# CONNECTOR.net
KiCad netlist of a schematic drawn in Altium Designer
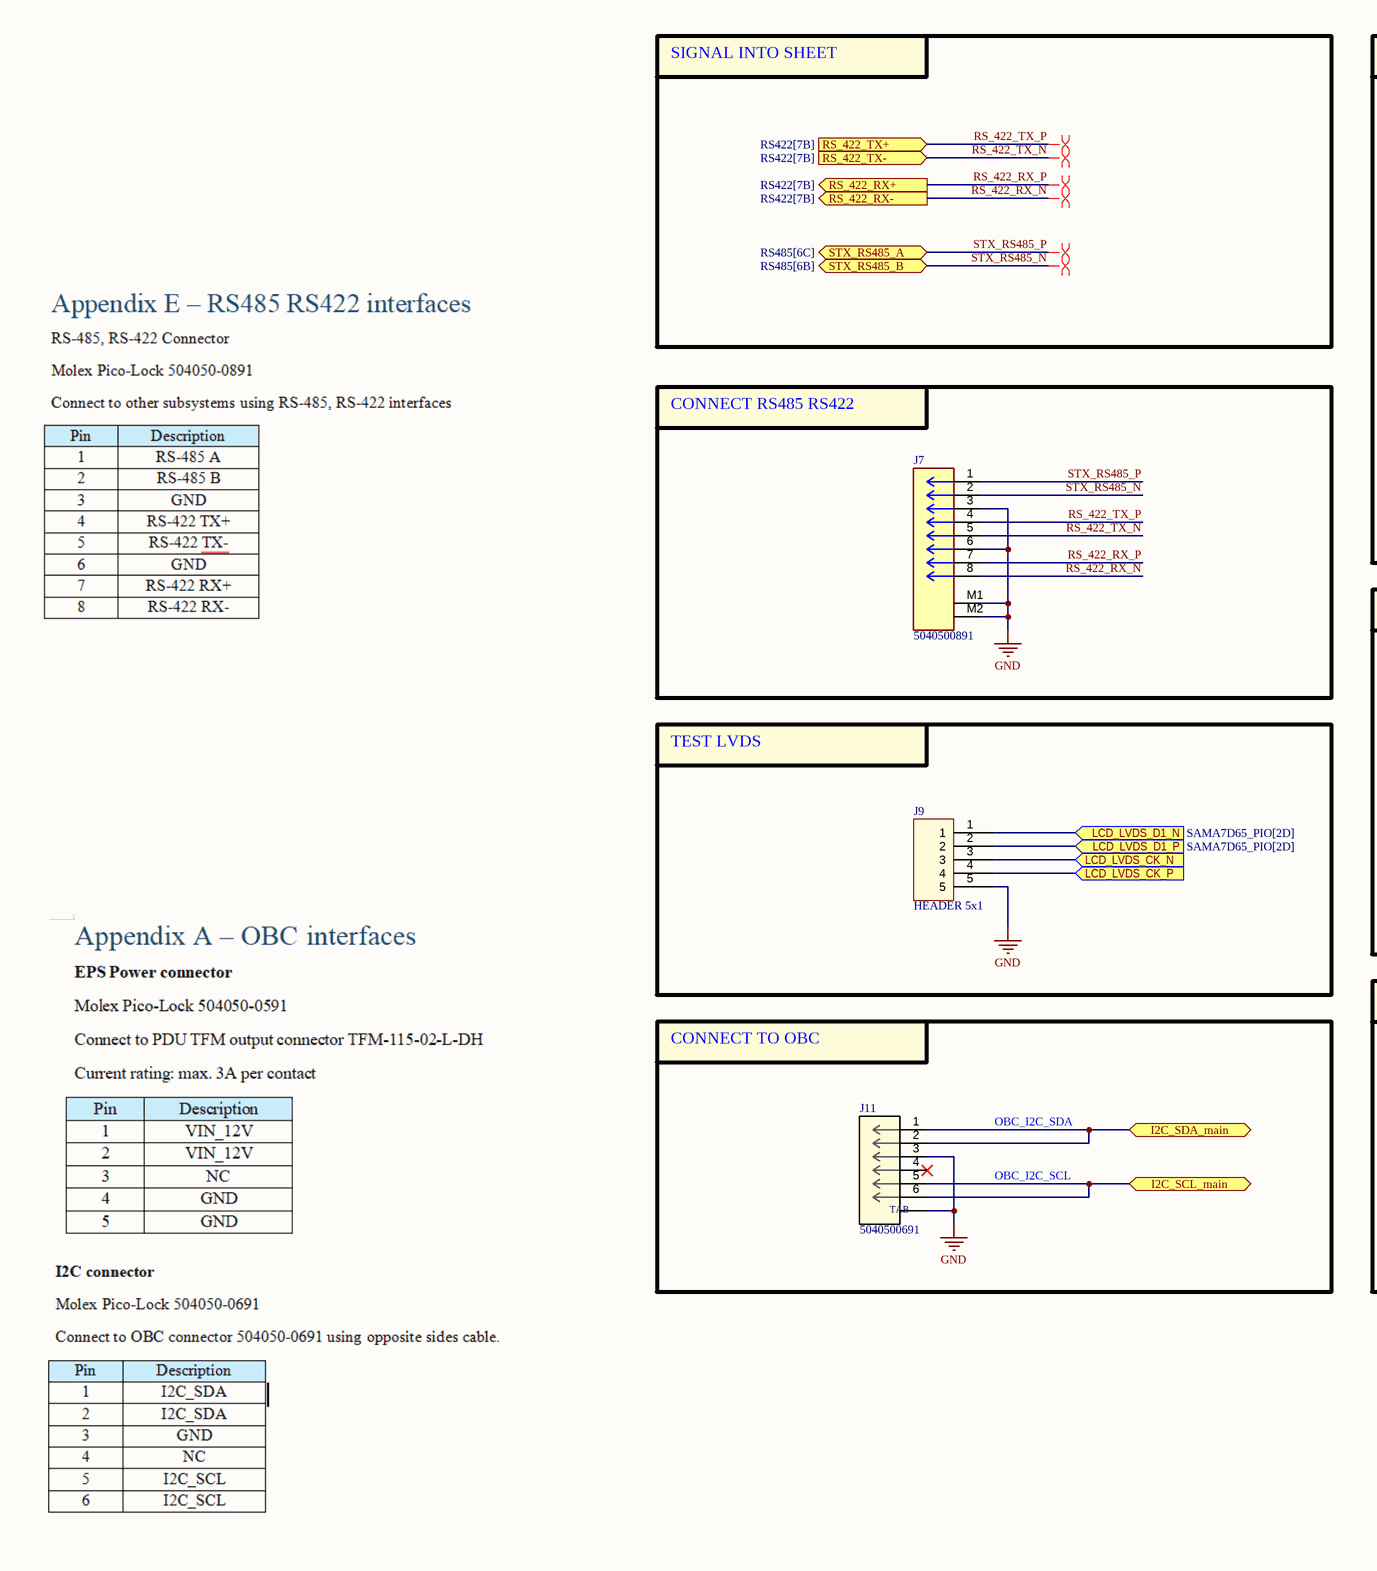
[diagram p0: CONNECTOR.SchDoc, left]
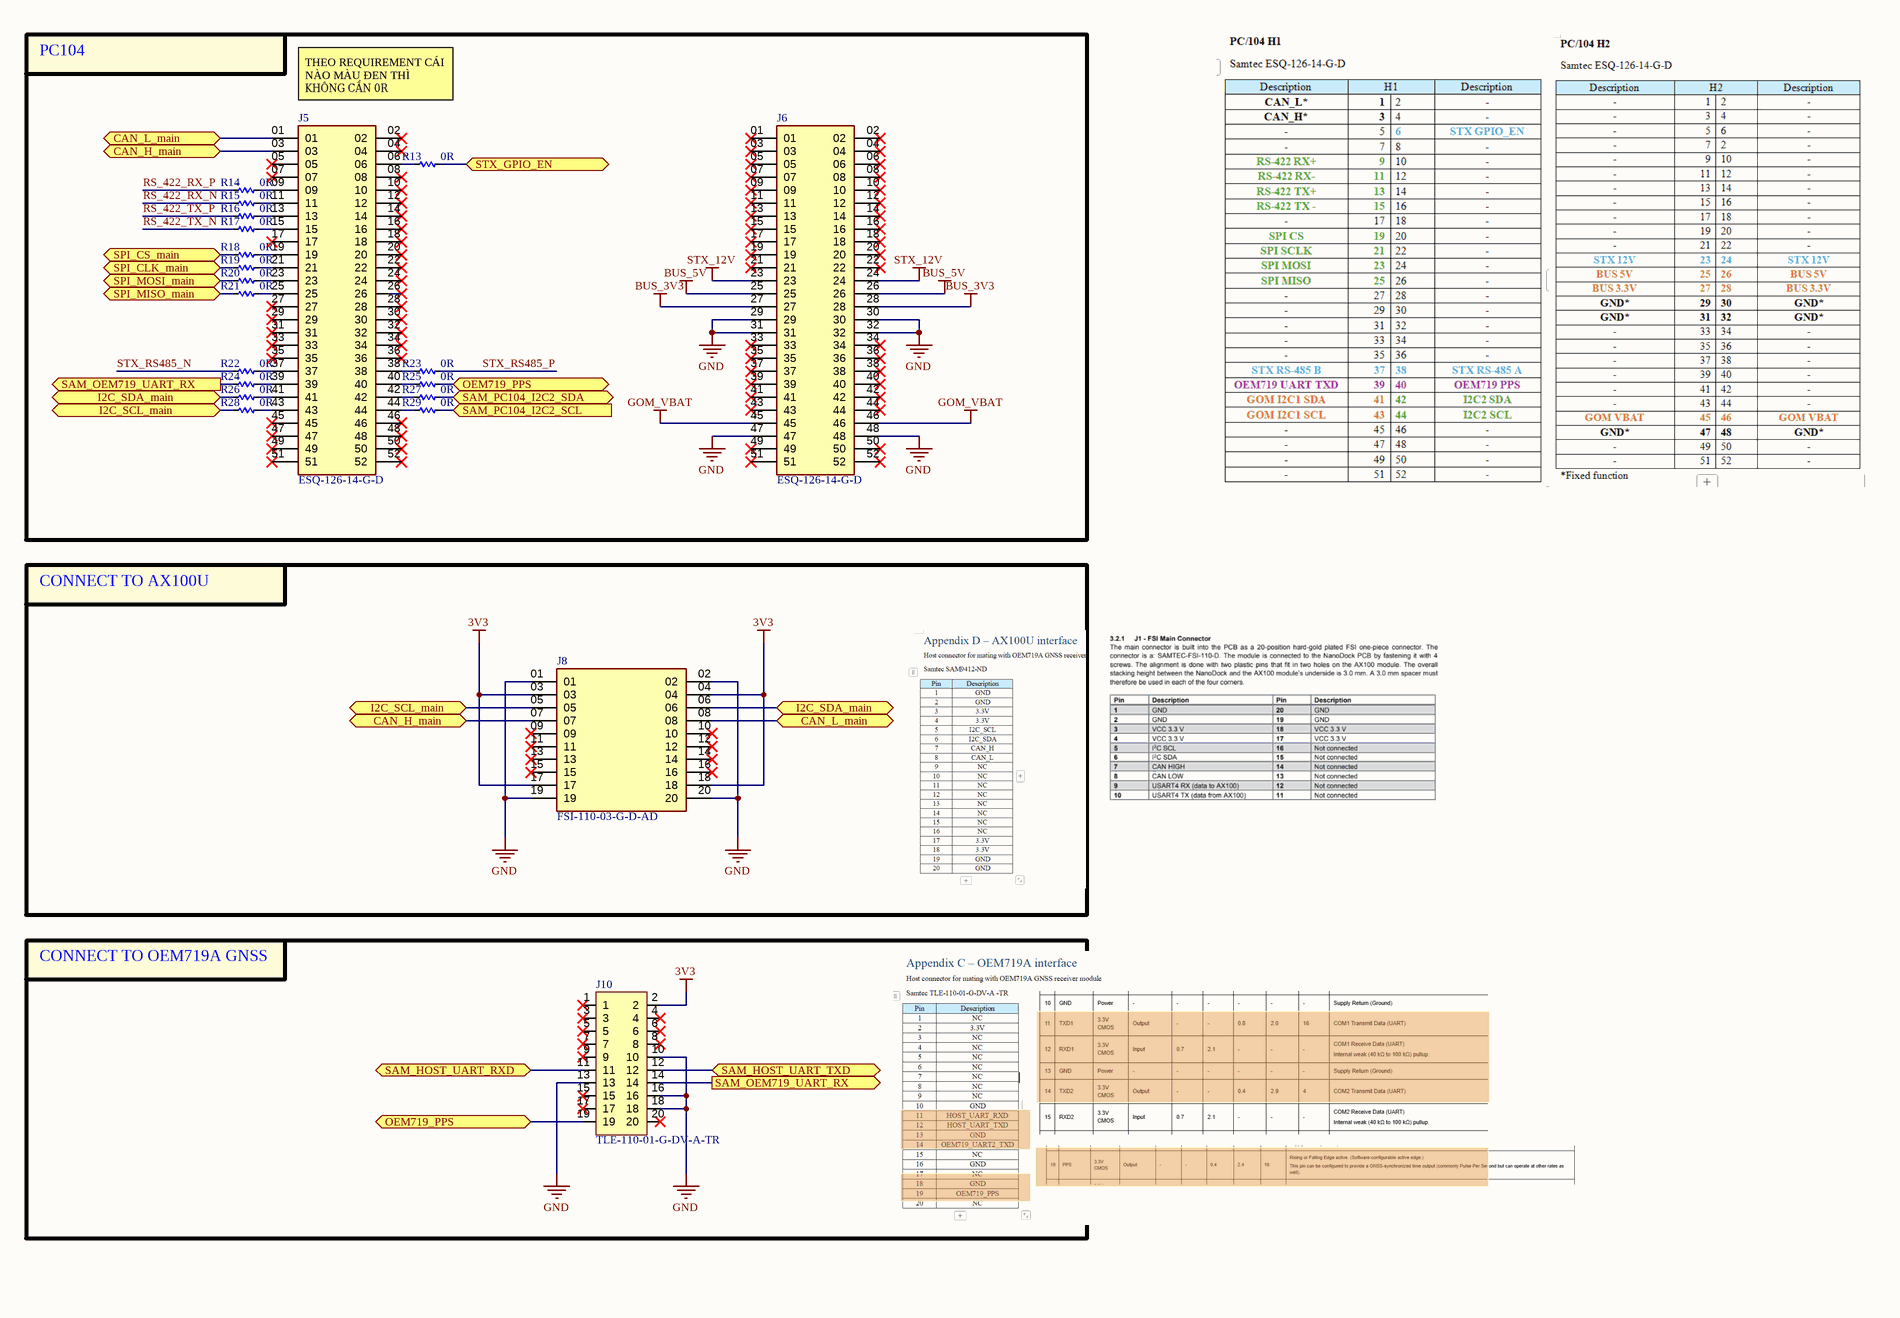
[diagram p1: CONNECTOR.SchDoc, right]

(export (version "E")
  (design (tool "Eeschema 10.0.6"))
  (components
    (comp (ref "J5")
      (value "ESQ-126-14-G-D")
      (footprint "ESQ-126-14-G-D")
      (description "CONN SOCKET 52POS 0.1 GOLD PCB")
      (fields (field (name "MF") "Samtec"))
      (libsource (lib "IFBschelib") (part "ESQ-126-14-G-D"))
    )
    (comp (ref "J6")
      (value "ESQ-126-14-G-D")
      (footprint "ESQ-126-14-G-D")
      (description "CONN SOCKET 52POS 0.1 GOLD PCB")
      (fields (field (name "MF") "Samtec"))
      (libsource (lib "IFBschelib") (part "ESQ-126-14-G-D"))
    )
    (comp (ref "J7")
      (value "5040500891")
      (footprint "MOLEX_5040500891")
      (description "Connector Header Surface Mount, Right Angle 8 position 0.059\" (1.50mm)`")
      (libsource (lib "IFBschelib") (part "5040500891"))
    )
    (comp (ref "J8")
      (value "FSI-110-03-G-D-AD")
      (footprint "SAMTEC_FSI-110-03-X-D-AD-TR")
      (description "CONN STACKING 20POS SMD GOLD")
      (fields (field (name "MP") "FSI-110-03-X-D-AD-TR"))
      (libsource (lib "IFBschelib") (part "FSI-110-03-X-D-AD-TR"))
    )
    (comp (ref "J9")
      (value "HEADER 5x1")
      (footprint "Header_254P_5x1")
      (libsource (lib "IFBschelib") (part "Header 5x1"))
    )
    (comp (ref "J10")
      (value "TLE-110-01-G-DV-A-TR")
      (footprint "SAMTEC-TLE-110-01-X-DV-A")
      (description "CONN RCPT 20POS 0.079 GOLD SMD")
      (fields (field (name "MP") "SAMTEC-TLE-110-01-X-DV-A"))
      (libsource (lib "IFBschelib") (part "SAMTEC-TLE-110-01-X-DV-A"))
    )
    (comp (ref "J11")
      (value "5040500691")
      (footprint "5040500691")
      (fields (field (name "COPYRIGHT") "Copyright (C) 2025 Ultra Librarian. All rights reserved."))
      (libsource (lib "IFBschelib") (part "5040500691"))
    )
    (comp (ref "R13")
      (value "0R")
      (footprint "RES_C_1005x30_L")
      (description "RES")
      (libsource (lib "IFBschelib") (part "_RES_B_2"))
    )
    (comp (ref "R14")
      (value "0R")
      (footprint "RES_C_1005x30_L")
      (description "RES")
      (libsource (lib "IFBschelib") (part "_RES_B_2"))
    )
    (comp (ref "R15")
      (value "0R")
      (footprint "RES_C_1005x30_L")
      (description "RES")
      (libsource (lib "IFBschelib") (part "_RES_B_2"))
    )
    (comp (ref "R16")
      (value "0R")
      (footprint "RES_C_1005x30_L")
      (description "RES")
      (libsource (lib "IFBschelib") (part "_RES_B_2"))
    )
    (comp (ref "R17")
      (value "0R")
      (footprint "RES_C_1005x30_L")
      (description "RES")
      (libsource (lib "IFBschelib") (part "_RES_B_2"))
    )
    (comp (ref "R18")
      (value "0R")
      (footprint "RES_C_1005x30_L")
      (description "RES")
      (libsource (lib "IFBschelib") (part "_RES_B_2"))
    )
    (comp (ref "R19")
      (value "0R")
      (footprint "RES_C_1005x30_L")
      (description "RES")
      (libsource (lib "IFBschelib") (part "_RES_B_2"))
    )
    (comp (ref "R20")
      (value "0R")
      (footprint "RES_C_1005x30_L")
      (description "RES")
      (libsource (lib "IFBschelib") (part "_RES_B_2"))
    )
    (comp (ref "R21")
      (value "0R")
      (footprint "RES_C_1005x30_L")
      (description "RES")
      (libsource (lib "IFBschelib") (part "_RES_B_2"))
    )
    (comp (ref "R22")
      (value "0R")
      (footprint "RES_C_1005x30_L")
      (description "RES")
      (libsource (lib "IFBschelib") (part "_RES_B_2"))
    )
    (comp (ref "R23")
      (value "0R")
      (footprint "RES_C_1005x30_L")
      (description "RES")
      (libsource (lib "IFBschelib") (part "_RES_B_2"))
    )
    (comp (ref "R24")
      (value "0R")
      (footprint "RES_C_1005x30_L")
      (description "RES")
      (libsource (lib "IFBschelib") (part "_RES_B_2"))
    )
    (comp (ref "R25")
      (value "0R")
      (footprint "RES_C_1005x30_L")
      (description "RES")
      (libsource (lib "IFBschelib") (part "_RES_B_2"))
    )
    (comp (ref "R26")
      (value "0R")
      (footprint "RES_C_1005x30_L")
      (description "RES")
      (libsource (lib "IFBschelib") (part "_RES_B_2"))
    )
    (comp (ref "R27")
      (value "0R")
      (footprint "RES_C_1005x30_L")
      (description "RES")
      (libsource (lib "IFBschelib") (part "_RES_B_2"))
    )
    (comp (ref "R28")
      (value "0R")
      (footprint "RES_C_1005x30_L")
      (description "RES")
      (libsource (lib "IFBschelib") (part "_RES_B_2"))
    )
    (comp (ref "R29")
      (value "0R")
      (footprint "RES_C_1005x30_L")
      (description "RES")
      (libsource (lib "IFBschelib") (part "_RES_B_2"))
    )
  )
  (nets
    (net (code "1") (name "/CAN_H_main") (class "Default")
      (node (ref "J5") (pin "03") (pinfunction "03_03") (pintype "passive"))
      (node (ref "J8") (pin "07") (pinfunction "07_07") (pintype "passive"))
    )
    (net (code "2") (name "/CAN_L_main") (class "Default")
      (node (ref "J5") (pin "01") (pinfunction "01_01") (pintype "passive"))
      (node (ref "J8") (pin "08") (pinfunction "08_08") (pintype "passive"))
    )
    (net (code "3") (name "/I2C_SCL_main") (class "Default")
      (node (ref "J11") (pin "5") (pinfunction "5_5") (pintype "passive"))
      (node (ref "J11") (pin "6") (pinfunction "6_6") (pintype "passive"))
      (node (ref "J8") (pin "05") (pinfunction "05_05") (pintype "passive"))
      (node (ref "R28") (pin "1") (pinfunction "1_1") (pintype "passive"))
    )
    (net (code "4") (name "/I2C_SDA_main") (class "Default")
      (node (ref "J11") (pin "1") (pinfunction "1_1") (pintype "passive"))
      (node (ref "J11") (pin "2") (pinfunction "2_2") (pintype "passive"))
      (node (ref "J8") (pin "06") (pinfunction "06_06") (pintype "passive"))
      (node (ref "R26") (pin "1") (pinfunction "1_1") (pintype "passive"))
    )
    (net (code "5") (name "/LCD_LVDS_CK_N") (class "Default")
      (node (ref "J9") (pin "3") (pinfunction "3_3") (pintype "passive"))
    )
    (net (code "6") (name "/LCD_LVDS_CK_P") (class "Default")
      (node (ref "J9") (pin "4") (pinfunction "4_4") (pintype "passive"))
    )
    (net (code "7") (name "/LCD_LVDS_D1_N") (class "Default")
      (node (ref "J9") (pin "1") (pinfunction "1_1") (pintype "passive"))
    )
    (net (code "8") (name "/LCD_LVDS_D1_P") (class "Default")
      (node (ref "J9") (pin "2") (pinfunction "2_2") (pintype "passive"))
    )
    (net (code "9") (name "/OEM719_PPS") (class "Default")
      (node (ref "J10") (pin "19") (pinfunction "19_19") (pintype "passive"))
      (node (ref "R25") (pin "2") (pinfunction "2_2") (pintype "passive"))
    )
    (net (code "10") (name "/RS_422_RX_N") (class "Default")
      (node (ref "J7") (pin "8") (pinfunction "8_8") (pintype "passive"))
      (node (ref "R15") (pin "1") (pinfunction "1_1") (pintype "passive"))
    )
    (net (code "11") (name "/RS_422_RX_P") (class "Default")
      (node (ref "J7") (pin "7") (pinfunction "7_7") (pintype "passive"))
      (node (ref "R14") (pin "1") (pinfunction "1_1") (pintype "passive"))
    )
    (net (code "12") (name "/RS_422_TX_N") (class "Default")
      (node (ref "J7") (pin "5") (pinfunction "5_5") (pintype "passive"))
      (node (ref "R17") (pin "1") (pinfunction "1_1") (pintype "passive"))
    )
    (net (code "13") (name "/RS_422_TX_P") (class "Default")
      (node (ref "J7") (pin "4") (pinfunction "4_4") (pintype "passive"))
      (node (ref "R16") (pin "1") (pinfunction "1_1") (pintype "passive"))
    )
    (net (code "14") (name "/SAM_HOST_UART_RXD") (class "Default")
      (node (ref "J10") (pin "11") (pinfunction "11_11") (pintype "passive"))
    )
    (net (code "15") (name "/SAM_HOST_UART_TXD") (class "Default")
      (node (ref "J10") (pin "12") (pinfunction "12_12") (pintype "passive"))
    )
    (net (code "16") (name "/SAM_OEM719_UART_RX") (class "Default")
      (node (ref "J10") (pin "14") (pinfunction "14_14") (pintype "passive"))
      (node (ref "R24") (pin "1") (pinfunction "1_1") (pintype "passive"))
    )
    (net (code "17") (name "/SAM_PC104_I2C2_SCL") (class "Default")
      (node (ref "R29") (pin "2") (pinfunction "2_2") (pintype "passive"))
    )
    (net (code "18") (name "/SAM_PC104_I2C2_SDA") (class "Default")
      (node (ref "R27") (pin "2") (pinfunction "2_2") (pintype "passive"))
    )
    (net (code "19") (name "/SPI_CLK_main") (class "Default")
      (node (ref "R19") (pin "1") (pinfunction "1_1") (pintype "passive"))
    )
    (net (code "20") (name "/SPI_CS_main") (class "Default")
      (node (ref "R18") (pin "1") (pinfunction "1_1") (pintype "passive"))
    )
    (net (code "21") (name "/SPI_MISO_main") (class "Default")
      (node (ref "R21") (pin "1") (pinfunction "1_1") (pintype "passive"))
    )
    (net (code "22") (name "/SPI_MOSI_main") (class "Default")
      (node (ref "R20") (pin "1") (pinfunction "1_1") (pintype "passive"))
    )
    (net (code "23") (name "/STX_GPIO_EN") (class "Default")
      (node (ref "R13") (pin "2") (pinfunction "2_2") (pintype "passive"))
    )
    (net (code "24") (name "/STX_RS485_N") (class "Default")
      (node (ref "J7") (pin "2") (pinfunction "2_2") (pintype "passive"))
      (node (ref "R22") (pin "1") (pinfunction "1_1") (pintype "passive"))
    )
    (net (code "25") (name "/STX_RS485_P") (class "Default")
      (node (ref "J7") (pin "1") (pinfunction "1_1") (pintype "passive"))
      (node (ref "R23") (pin "2") (pinfunction "2_2") (pintype "passive"))
    )
    (net (code "26") (name "3V3") (class "Default")
      (node (ref "J10") (pin "2") (pinfunction "2_2") (pintype "passive"))
      (node (ref "J8") (pin "03") (pinfunction "03_03") (pintype "passive"))
      (node (ref "J8") (pin "04") (pinfunction "04_04") (pintype "passive"))
      (node (ref "J8") (pin "17") (pinfunction "17_17") (pintype "passive"))
      (node (ref "J8") (pin "18") (pinfunction "18_18") (pintype "passive"))
    )
    (net (code "27") (name "BUS_3V3") (class "Default")
      (node (ref "J6") (pin "27") (pinfunction "27_27") (pintype "passive"))
      (node (ref "J6") (pin "28") (pinfunction "28_28") (pintype "passive"))
    )
    (net (code "28") (name "BUS_5V") (class "Default")
      (node (ref "J6") (pin "25") (pinfunction "25_25") (pintype "passive"))
      (node (ref "J6") (pin "26") (pinfunction "26_26") (pintype "passive"))
    )
    (net (code "29") (name "GND") (class "Default")
      (node (ref "J10") (pin "10") (pinfunction "10_10") (pintype "passive"))
      (node (ref "J10") (pin "13") (pinfunction "13_13") (pintype "passive"))
      (node (ref "J10") (pin "16") (pinfunction "16_16") (pintype "passive"))
      (node (ref "J10") (pin "18") (pinfunction "18_18") (pintype "passive"))
      (node (ref "J11") (pin "3") (pinfunction "3_3") (pintype "passive"))
      (node (ref "J11") (pin "7") (pinfunction "7_7") (pintype "passive"))
      (node (ref "J6") (pin "29") (pinfunction "29_29") (pintype "passive"))
      (node (ref "J6") (pin "30") (pinfunction "30_30") (pintype "passive"))
      (node (ref "J6") (pin "31") (pinfunction "31_31") (pintype "passive"))
      (node (ref "J6") (pin "32") (pinfunction "32_32") (pintype "passive"))
      (node (ref "J6") (pin "47") (pinfunction "47_47") (pintype "passive"))
      (node (ref "J6") (pin "48") (pinfunction "48_48") (pintype "passive"))
      (node (ref "J7") (pin "3") (pinfunction "3_3") (pintype "passive"))
      (node (ref "J7") (pin "6") (pinfunction "6_6") (pintype "passive"))
      (node (ref "J7") (pin "M1") (pinfunction "M1_M1") (pintype "passive"))
      (node (ref "J7") (pin "M2") (pinfunction "M2_M2") (pintype "passive"))
      (node (ref "J8") (pin "01") (pinfunction "01_01") (pintype "passive"))
      (node (ref "J8") (pin "02") (pinfunction "02_02") (pintype "passive"))
      (node (ref "J8") (pin "19") (pinfunction "19_19") (pintype "passive"))
      (node (ref "J8") (pin "20") (pinfunction "20_20") (pintype "passive"))
      (node (ref "J9") (pin "5") (pinfunction "5_5") (pintype "passive"))
    )
    (net (code "30") (name "GOM_VBAT") (class "Default")
      (node (ref "J6") (pin "45") (pinfunction "45_45") (pintype "passive"))
      (node (ref "J6") (pin "46") (pinfunction "46_46") (pintype "passive"))
    )
    (net (code "31") (name "Net-(J5-Pad06)") (class "Default")
      (node (ref "J5") (pin "06") (pinfunction "06_06") (pintype "passive"))
      (node (ref "R13") (pin "1") (pinfunction "1_1") (pintype "passive"))
    )
    (net (code "32") (name "Net-(J5-Pad09)") (class "Default")
      (node (ref "J5") (pin "09") (pinfunction "09_09") (pintype "passive"))
      (node (ref "R14") (pin "2") (pinfunction "2_2") (pintype "passive"))
    )
    (net (code "33") (name "Net-(J5-Pad11)") (class "Default")
      (node (ref "J5") (pin "11") (pinfunction "11_11") (pintype "passive"))
      (node (ref "R15") (pin "2") (pinfunction "2_2") (pintype "passive"))
    )
    (net (code "34") (name "Net-(J5-Pad13)") (class "Default")
      (node (ref "J5") (pin "13") (pinfunction "13_13") (pintype "passive"))
      (node (ref "R16") (pin "2") (pinfunction "2_2") (pintype "passive"))
    )
    (net (code "35") (name "Net-(J5-Pad15)") (class "Default")
      (node (ref "J5") (pin "15") (pinfunction "15_15") (pintype "passive"))
      (node (ref "R17") (pin "2") (pinfunction "2_2") (pintype "passive"))
    )
    (net (code "36") (name "Net-(J5-Pad19)") (class "Default")
      (node (ref "J5") (pin "19") (pinfunction "19_19") (pintype "passive"))
      (node (ref "R18") (pin "2") (pinfunction "2_2") (pintype "passive"))
    )
    (net (code "37") (name "Net-(J5-Pad21)") (class "Default")
      (node (ref "J5") (pin "21") (pinfunction "21_21") (pintype "passive"))
      (node (ref "R19") (pin "2") (pinfunction "2_2") (pintype "passive"))
    )
    (net (code "38") (name "Net-(J5-Pad23)") (class "Default")
      (node (ref "J5") (pin "23") (pinfunction "23_23") (pintype "passive"))
      (node (ref "R20") (pin "2") (pinfunction "2_2") (pintype "passive"))
    )
    (net (code "39") (name "Net-(J5-Pad25)") (class "Default")
      (node (ref "J5") (pin "25") (pinfunction "25_25") (pintype "passive"))
      (node (ref "R21") (pin "2") (pinfunction "2_2") (pintype "passive"))
    )
    (net (code "40") (name "Net-(J5-Pad37)") (class "Default")
      (node (ref "J5") (pin "37") (pinfunction "37_37") (pintype "passive"))
      (node (ref "R22") (pin "2") (pinfunction "2_2") (pintype "passive"))
    )
    (net (code "41") (name "Net-(J5-Pad38)") (class "Default")
      (node (ref "J5") (pin "38") (pinfunction "38_38") (pintype "passive"))
      (node (ref "R23") (pin "1") (pinfunction "1_1") (pintype "passive"))
    )
    (net (code "42") (name "Net-(J5-Pad39)") (class "Default")
      (node (ref "J5") (pin "39") (pinfunction "39_39") (pintype "passive"))
      (node (ref "R24") (pin "2") (pinfunction "2_2") (pintype "passive"))
    )
    (net (code "43") (name "Net-(J5-Pad40)") (class "Default")
      (node (ref "J5") (pin "40") (pinfunction "40_40") (pintype "passive"))
      (node (ref "R25") (pin "1") (pinfunction "1_1") (pintype "passive"))
    )
    (net (code "44") (name "Net-(J5-Pad41)") (class "Default")
      (node (ref "J5") (pin "41") (pinfunction "41_41") (pintype "passive"))
      (node (ref "R26") (pin "2") (pinfunction "2_2") (pintype "passive"))
    )
    (net (code "45") (name "Net-(J5-Pad42)") (class "Default")
      (node (ref "J5") (pin "42") (pinfunction "42_42") (pintype "passive"))
      (node (ref "R27") (pin "1") (pinfunction "1_1") (pintype "passive"))
    )
    (net (code "46") (name "Net-(J5-Pad43)") (class "Default")
      (node (ref "J5") (pin "43") (pinfunction "43_43") (pintype "passive"))
      (node (ref "R28") (pin "2") (pinfunction "2_2") (pintype "passive"))
    )
    (net (code "47") (name "Net-(J5-Pad44)") (class "Default")
      (node (ref "J5") (pin "44") (pinfunction "44_44") (pintype "passive"))
      (node (ref "R29") (pin "1") (pinfunction "1_1") (pintype "passive"))
    )
    (net (code "48") (name "STX_12V") (class "Default")
      (node (ref "J6") (pin "23") (pinfunction "23_23") (pintype "passive"))
      (node (ref "J6") (pin "24") (pinfunction "24_24") (pintype "passive"))
    )
    (net (code "49") (name "unconnected-(J5-Pad02)") (class "Default")
      (node (ref "J5") (pin "02") (pinfunction "02_02") (pintype "passive+no_connect"))
    )
    (net (code "50") (name "unconnected-(J5-Pad04)") (class "Default")
      (node (ref "J5") (pin "04") (pinfunction "04_04") (pintype "passive+no_connect"))
    )
    (net (code "51") (name "unconnected-(J5-Pad05)") (class "Default")
      (node (ref "J5") (pin "05") (pinfunction "05_05") (pintype "passive+no_connect"))
    )
    (net (code "52") (name "unconnected-(J5-Pad07)") (class "Default")
      (node (ref "J5") (pin "07") (pinfunction "07_07") (pintype "passive+no_connect"))
    )
    (net (code "53") (name "unconnected-(J5-Pad08)") (class "Default")
      (node (ref "J5") (pin "08") (pinfunction "08_08") (pintype "passive+no_connect"))
    )
    (net (code "54") (name "unconnected-(J5-Pad10)") (class "Default")
      (node (ref "J5") (pin "10") (pinfunction "10_10") (pintype "passive+no_connect"))
    )
    (net (code "55") (name "unconnected-(J5-Pad12)") (class "Default")
      (node (ref "J5") (pin "12") (pinfunction "12_12") (pintype "passive+no_connect"))
    )
    (net (code "56") (name "unconnected-(J5-Pad14)") (class "Default")
      (node (ref "J5") (pin "14") (pinfunction "14_14") (pintype "passive+no_connect"))
    )
    (net (code "57") (name "unconnected-(J5-Pad16)") (class "Default")
      (node (ref "J5") (pin "16") (pinfunction "16_16") (pintype "passive+no_connect"))
    )
    (net (code "58") (name "unconnected-(J5-Pad17)") (class "Default")
      (node (ref "J5") (pin "17") (pinfunction "17_17") (pintype "passive+no_connect"))
    )
    (net (code "59") (name "unconnected-(J5-Pad18)") (class "Default")
      (node (ref "J5") (pin "18") (pinfunction "18_18") (pintype "passive+no_connect"))
    )
    (net (code "60") (name "unconnected-(J5-Pad20)") (class "Default")
      (node (ref "J5") (pin "20") (pinfunction "20_20") (pintype "passive+no_connect"))
    )
    (net (code "61") (name "unconnected-(J5-Pad22)") (class "Default")
      (node (ref "J5") (pin "22") (pinfunction "22_22") (pintype "passive+no_connect"))
    )
    (net (code "62") (name "unconnected-(J5-Pad24)") (class "Default")
      (node (ref "J5") (pin "24") (pinfunction "24_24") (pintype "passive+no_connect"))
    )
    (net (code "63") (name "unconnected-(J5-Pad26)") (class "Default")
      (node (ref "J5") (pin "26") (pinfunction "26_26") (pintype "passive+no_connect"))
    )
    (net (code "64") (name "unconnected-(J5-Pad27)") (class "Default")
      (node (ref "J5") (pin "27") (pinfunction "27_27") (pintype "passive+no_connect"))
    )
    (net (code "65") (name "unconnected-(J5-Pad28)") (class "Default")
      (node (ref "J5") (pin "28") (pinfunction "28_28") (pintype "passive+no_connect"))
    )
    (net (code "66") (name "unconnected-(J5-Pad29)") (class "Default")
      (node (ref "J5") (pin "29") (pinfunction "29_29") (pintype "passive+no_connect"))
    )
    (net (code "67") (name "unconnected-(J5-Pad30)") (class "Default")
      (node (ref "J5") (pin "30") (pinfunction "30_30") (pintype "passive+no_connect"))
    )
    (net (code "68") (name "unconnected-(J5-Pad31)") (class "Default")
      (node (ref "J5") (pin "31") (pinfunction "31_31") (pintype "passive+no_connect"))
    )
    (net (code "69") (name "unconnected-(J5-Pad32)") (class "Default")
      (node (ref "J5") (pin "32") (pinfunction "32_32") (pintype "passive+no_connect"))
    )
    (net (code "70") (name "unconnected-(J5-Pad33)") (class "Default")
      (node (ref "J5") (pin "33") (pinfunction "33_33") (pintype "passive+no_connect"))
    )
    (net (code "71") (name "unconnected-(J5-Pad34)") (class "Default")
      (node (ref "J5") (pin "34") (pinfunction "34_34") (pintype "passive+no_connect"))
    )
    (net (code "72") (name "unconnected-(J5-Pad35)") (class "Default")
      (node (ref "J5") (pin "35") (pinfunction "35_35") (pintype "passive+no_connect"))
    )
    (net (code "73") (name "unconnected-(J5-Pad36)") (class "Default")
      (node (ref "J5") (pin "36") (pinfunction "36_36") (pintype "passive+no_connect"))
    )
    (net (code "74") (name "unconnected-(J5-Pad45)") (class "Default")
      (node (ref "J5") (pin "45") (pinfunction "45_45") (pintype "passive+no_connect"))
    )
    (net (code "75") (name "unconnected-(J5-Pad46)") (class "Default")
      (node (ref "J5") (pin "46") (pinfunction "46_46") (pintype "passive+no_connect"))
    )
    (net (code "76") (name "unconnected-(J5-Pad47)") (class "Default")
      (node (ref "J5") (pin "47") (pinfunction "47_47") (pintype "passive+no_connect"))
    )
    (net (code "77") (name "unconnected-(J5-Pad48)") (class "Default")
      (node (ref "J5") (pin "48") (pinfunction "48_48") (pintype "passive+no_connect"))
    )
    (net (code "78") (name "unconnected-(J5-Pad49)") (class "Default")
      (node (ref "J5") (pin "49") (pinfunction "49_49") (pintype "passive+no_connect"))
    )
    (net (code "79") (name "unconnected-(J5-Pad50)") (class "Default")
      (node (ref "J5") (pin "50") (pinfunction "50_50") (pintype "passive+no_connect"))
    )
    (net (code "80") (name "unconnected-(J5-Pad51)") (class "Default")
      (node (ref "J5") (pin "51") (pinfunction "51_51") (pintype "passive+no_connect"))
    )
    (net (code "81") (name "unconnected-(J5-Pad52)") (class "Default")
      (node (ref "J5") (pin "52") (pinfunction "52_52") (pintype "passive+no_connect"))
    )
    (net (code "82") (name "unconnected-(J6-Pad01)") (class "Default")
      (node (ref "J6") (pin "01") (pinfunction "01_01") (pintype "passive+no_connect"))
    )
    (net (code "83") (name "unconnected-(J6-Pad02)") (class "Default")
      (node (ref "J6") (pin "02") (pinfunction "02_02") (pintype "passive+no_connect"))
    )
    (net (code "84") (name "unconnected-(J6-Pad03)") (class "Default")
      (node (ref "J6") (pin "03") (pinfunction "03_03") (pintype "passive+no_connect"))
    )
    (net (code "85") (name "unconnected-(J6-Pad04)") (class "Default")
      (node (ref "J6") (pin "04") (pinfunction "04_04") (pintype "passive+no_connect"))
    )
    (net (code "86") (name "unconnected-(J6-Pad05)") (class "Default")
      (node (ref "J6") (pin "05") (pinfunction "05_05") (pintype "passive+no_connect"))
    )
    (net (code "87") (name "unconnected-(J6-Pad06)") (class "Default")
      (node (ref "J6") (pin "06") (pinfunction "06_06") (pintype "passive+no_connect"))
    )
    (net (code "88") (name "unconnected-(J6-Pad07)") (class "Default")
      (node (ref "J6") (pin "07") (pinfunction "07_07") (pintype "passive+no_connect"))
    )
    (net (code "89") (name "unconnected-(J6-Pad08)") (class "Default")
      (node (ref "J6") (pin "08") (pinfunction "08_08") (pintype "passive+no_connect"))
    )
    (net (code "90") (name "unconnected-(J6-Pad09)") (class "Default")
      (node (ref "J6") (pin "09") (pinfunction "09_09") (pintype "passive+no_connect"))
    )
    (net (code "91") (name "unconnected-(J6-Pad10)") (class "Default")
      (node (ref "J6") (pin "10") (pinfunction "10_10") (pintype "passive+no_connect"))
    )
    (net (code "92") (name "unconnected-(J6-Pad11)") (class "Default")
      (node (ref "J6") (pin "11") (pinfunction "11_11") (pintype "passive+no_connect"))
    )
    (net (code "93") (name "unconnected-(J6-Pad12)") (class "Default")
      (node (ref "J6") (pin "12") (pinfunction "12_12") (pintype "passive+no_connect"))
    )
    (net (code "94") (name "unconnected-(J6-Pad13)") (class "Default")
      (node (ref "J6") (pin "13") (pinfunction "13_13") (pintype "passive+no_connect"))
    )
    (net (code "95") (name "unconnected-(J6-Pad14)") (class "Default")
      (node (ref "J6") (pin "14") (pinfunction "14_14") (pintype "passive+no_connect"))
    )
    (net (code "96") (name "unconnected-(J6-Pad15)") (class "Default")
      (node (ref "J6") (pin "15") (pinfunction "15_15") (pintype "passive+no_connect"))
    )
    (net (code "97") (name "unconnected-(J6-Pad16)") (class "Default")
      (node (ref "J6") (pin "16") (pinfunction "16_16") (pintype "passive+no_connect"))
    )
    (net (code "98") (name "unconnected-(J6-Pad17)") (class "Default")
      (node (ref "J6") (pin "17") (pinfunction "17_17") (pintype "passive+no_connect"))
    )
    (net (code "99") (name "unconnected-(J6-Pad18)") (class "Default")
      (node (ref "J6") (pin "18") (pinfunction "18_18") (pintype "passive+no_connect"))
    )
    (net (code "100") (name "unconnected-(J6-Pad19)") (class "Default")
      (node (ref "J6") (pin "19") (pinfunction "19_19") (pintype "passive+no_connect"))
    )
    (net (code "101") (name "unconnected-(J6-Pad20)") (class "Default")
      (node (ref "J6") (pin "20") (pinfunction "20_20") (pintype "passive+no_connect"))
    )
    (net (code "102") (name "unconnected-(J6-Pad21)") (class "Default")
      (node (ref "J6") (pin "21") (pinfunction "21_21") (pintype "passive+no_connect"))
    )
    (net (code "103") (name "unconnected-(J6-Pad22)") (class "Default")
      (node (ref "J6") (pin "22") (pinfunction "22_22") (pintype "passive+no_connect"))
    )
    (net (code "104") (name "unconnected-(J6-Pad33)") (class "Default")
      (node (ref "J6") (pin "33") (pinfunction "33_33") (pintype "passive+no_connect"))
    )
    (net (code "105") (name "unconnected-(J6-Pad34)") (class "Default")
      (node (ref "J6") (pin "34") (pinfunction "34_34") (pintype "passive+no_connect"))
    )
    (net (code "106") (name "unconnected-(J6-Pad35)") (class "Default")
      (node (ref "J6") (pin "35") (pinfunction "35_35") (pintype "passive+no_connect"))
    )
    (net (code "107") (name "unconnected-(J6-Pad36)") (class "Default")
      (node (ref "J6") (pin "36") (pinfunction "36_36") (pintype "passive+no_connect"))
    )
    (net (code "108") (name "unconnected-(J6-Pad37)") (class "Default")
      (node (ref "J6") (pin "37") (pinfunction "37_37") (pintype "passive+no_connect"))
    )
    (net (code "109") (name "unconnected-(J6-Pad38)") (class "Default")
      (node (ref "J6") (pin "38") (pinfunction "38_38") (pintype "passive+no_connect"))
    )
    (net (code "110") (name "unconnected-(J6-Pad39)") (class "Default")
      (node (ref "J6") (pin "39") (pinfunction "39_39") (pintype "passive+no_connect"))
    )
    (net (code "111") (name "unconnected-(J6-Pad40)") (class "Default")
      (node (ref "J6") (pin "40") (pinfunction "40_40") (pintype "passive+no_connect"))
    )
    (net (code "112") (name "unconnected-(J6-Pad41)") (class "Default")
      (node (ref "J6") (pin "41") (pinfunction "41_41") (pintype "passive+no_connect"))
    )
    (net (code "113") (name "unconnected-(J6-Pad42)") (class "Default")
      (node (ref "J6") (pin "42") (pinfunction "42_42") (pintype "passive+no_connect"))
    )
    (net (code "114") (name "unconnected-(J6-Pad43)") (class "Default")
      (node (ref "J6") (pin "43") (pinfunction "43_43") (pintype "passive+no_connect"))
    )
    (net (code "115") (name "unconnected-(J6-Pad44)") (class "Default")
      (node (ref "J6") (pin "44") (pinfunction "44_44") (pintype "passive+no_connect"))
    )
    (net (code "116") (name "unconnected-(J6-Pad49)") (class "Default")
      (node (ref "J6") (pin "49") (pinfunction "49_49") (pintype "passive+no_connect"))
    )
    (net (code "117") (name "unconnected-(J6-Pad50)") (class "Default")
      (node (ref "J6") (pin "50") (pinfunction "50_50") (pintype "passive+no_connect"))
    )
    (net (code "118") (name "unconnected-(J6-Pad51)") (class "Default")
      (node (ref "J6") (pin "51") (pinfunction "51_51") (pintype "passive+no_connect"))
    )
    (net (code "119") (name "unconnected-(J6-Pad52)") (class "Default")
      (node (ref "J6") (pin "52") (pinfunction "52_52") (pintype "passive+no_connect"))
    )
    (net (code "120") (name "unconnected-(J8-Pad09)") (class "Default")
      (node (ref "J8") (pin "09") (pinfunction "09_09") (pintype "passive+no_connect"))
    )
    (net (code "121") (name "unconnected-(J8-Pad10)") (class "Default")
      (node (ref "J8") (pin "10") (pinfunction "10_10") (pintype "passive+no_connect"))
    )
    (net (code "122") (name "unconnected-(J8-Pad11)") (class "Default")
      (node (ref "J8") (pin "11") (pinfunction "11_11") (pintype "passive+no_connect"))
    )
    (net (code "123") (name "unconnected-(J8-Pad12)") (class "Default")
      (node (ref "J8") (pin "12") (pinfunction "12_12") (pintype "passive+no_connect"))
    )
    (net (code "124") (name "unconnected-(J8-Pad13)") (class "Default")
      (node (ref "J8") (pin "13") (pinfunction "13_13") (pintype "passive+no_connect"))
    )
    (net (code "125") (name "unconnected-(J8-Pad14)") (class "Default")
      (node (ref "J8") (pin "14") (pinfunction "14_14") (pintype "passive+no_connect"))
    )
    (net (code "126") (name "unconnected-(J8-Pad15)") (class "Default")
      (node (ref "J8") (pin "15") (pinfunction "15_15") (pintype "passive+no_connect"))
    )
    (net (code "127") (name "unconnected-(J8-Pad16)") (class "Default")
      (node (ref "J8") (pin "16") (pinfunction "16_16") (pintype "passive+no_connect"))
    )
    (net (code "128") (name "unconnected-(J10-Pad1)") (class "Default")
      (node (ref "J10") (pin "1") (pinfunction "1_1") (pintype "passive+no_connect"))
    )
    (net (code "129") (name "unconnected-(J10-Pad3)") (class "Default")
      (node (ref "J10") (pin "3") (pinfunction "3_3") (pintype "passive+no_connect"))
    )
    (net (code "130") (name "unconnected-(J10-Pad4)") (class "Default")
      (node (ref "J10") (pin "4") (pinfunction "4_4") (pintype "passive+no_connect"))
    )
    (net (code "131") (name "unconnected-(J10-Pad5)") (class "Default")
      (node (ref "J10") (pin "5") (pinfunction "5_5") (pintype "passive+no_connect"))
    )
    (net (code "132") (name "unconnected-(J10-Pad6)") (class "Default")
      (node (ref "J10") (pin "6") (pinfunction "6_6") (pintype "passive+no_connect"))
    )
    (net (code "133") (name "unconnected-(J10-Pad7)") (class "Default")
      (node (ref "J10") (pin "7") (pinfunction "7_7") (pintype "passive+no_connect"))
    )
    (net (code "134") (name "unconnected-(J10-Pad8)") (class "Default")
      (node (ref "J10") (pin "8") (pinfunction "8_8") (pintype "passive+no_connect"))
    )
    (net (code "135") (name "unconnected-(J10-Pad9)") (class "Default")
      (node (ref "J10") (pin "9") (pinfunction "9_9") (pintype "passive+no_connect"))
    )
    (net (code "136") (name "unconnected-(J10-Pad15)") (class "Default")
      (node (ref "J10") (pin "15") (pinfunction "15_15") (pintype "passive+no_connect"))
    )
    (net (code "137") (name "unconnected-(J10-Pad17)") (class "Default")
      (node (ref "J10") (pin "17") (pinfunction "17_17") (pintype "passive+no_connect"))
    )
    (net (code "138") (name "unconnected-(J10-Pad20)") (class "Default")
      (node (ref "J10") (pin "20") (pinfunction "20_20") (pintype "passive+no_connect"))
    )
    (net (code "139") (name "unconnected-(J11-Pad4)") (class "Default")
      (node (ref "J11") (pin "4") (pinfunction "4_4") (pintype "passive+no_connect"))
    )
  )
)
